# Audio.net
KiCad netlist of a schematic drawn in Altium Designer
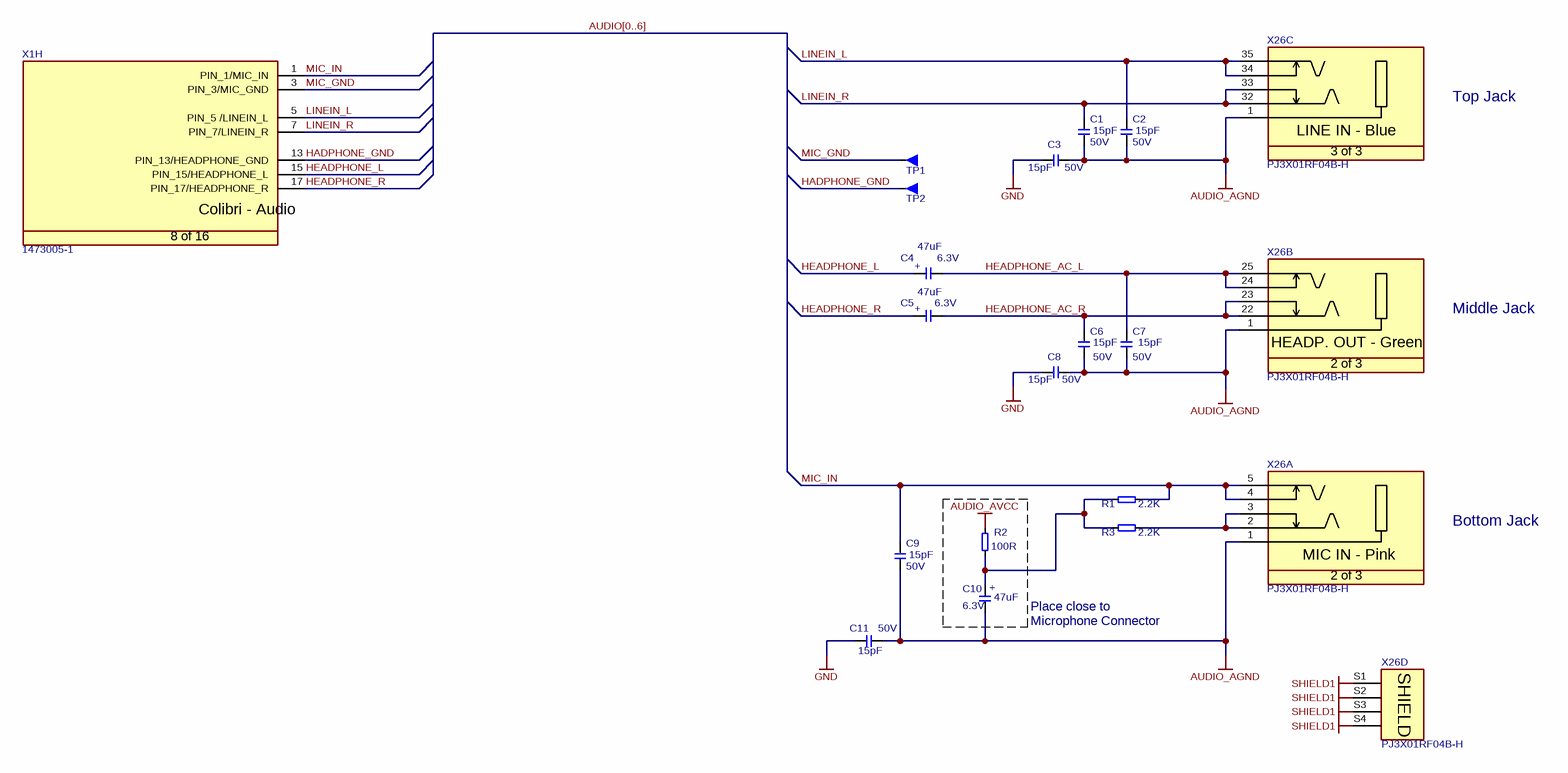
[diagram p0: Audio.SchDoc]

(export (version "E")
  (design (tool "Eeschema 10.0.6"))
  (components
    (comp (ref "C1")
      (value "15pF")
      (footprint "T_CAPC0603X33N")
      (description "Capacitor Ceramic NPO 15pF 50V 10% 0603")
      (fields (field (name "TOLERANCE") "10%") (field (name "RATING") "50V"))
      (libsource (lib "Evaluation Board") (part "C-NPO-15pF-50V-10%-0603"))
    )
    (comp (ref "C2")
      (value "15pF")
      (footprint "T_CAPC0603X33N")
      (description "Capacitor Ceramic NPO 15pF 50V 10% 0603")
      (fields (field (name "TOLERANCE") "10%") (field (name "RATING") "50V"))
      (libsource (lib "Evaluation Board") (part "C-NPO-15pF-50V-10%-0603"))
    )
    (comp (ref "C3")
      (value "15pF")
      (footprint "T_CAPC0603X33N")
      (description "Capacitor Ceramic NPO 15pF 50V 10% 0603")
      (fields (field (name "TOLERANCE") "10%") (field (name "RATING") "50V"))
      (libsource (lib "Evaluation Board") (part "C-NPO-15pF-50V-10%-0603"))
    )
    (comp (ref "C4")
      (value "47uF")
      (footprint "CAPMP3528X210N")
      (description "Capacitor TA 47uF 6.3V 20% 3216")
      (fields (field (name "TOLERANCE") "20%") (field (name "RATING") "6.3V"))
      (libsource (lib "Evaluation Board") (part "C-TA-47uF-6.3V-20%-3216"))
    )
    (comp (ref "C5")
      (value "47uF")
      (footprint "CAPMP3528X210N")
      (description "Capacitor TA 47uF 6.3V 20% 3216")
      (fields (field (name "TOLERANCE") "20%") (field (name "RATING") "6.3V"))
      (libsource (lib "Evaluation Board") (part "C-TA-47uF-6.3V-20%-3216"))
    )
    (comp (ref "C6")
      (value "15pF")
      (footprint "T_CAPC0603X33N")
      (description "Capacitor Ceramic NPO 15pF 50V 10% 0603")
      (fields (field (name "TOLERANCE") "10%") (field (name "RATING") "50V"))
      (libsource (lib "Evaluation Board") (part "C-NPO-15pF-50V-10%-0603"))
    )
    (comp (ref "C7")
      (value "15pF")
      (footprint "T_CAPC0603X33N")
      (description "Capacitor Ceramic NPO 15pF 50V 10% 0603")
      (fields (field (name "TOLERANCE") "10%") (field (name "RATING") "50V"))
      (libsource (lib "Evaluation Board") (part "C-NPO-15pF-50V-10%-0603"))
    )
    (comp (ref "C8")
      (value "15pF")
      (footprint "T_CAPC0603X33N")
      (description "Capacitor Ceramic NPO 15pF 50V 10% 0603")
      (fields (field (name "TOLERANCE") "10%") (field (name "RATING") "50V"))
      (libsource (lib "Evaluation Board") (part "C-NPO-15pF-50V-10%-0603"))
    )
    (comp (ref "C9")
      (value "15pF")
      (footprint "T_CAPC0603X33N")
      (description "Capacitor Ceramic NPO 15pF 50V 10% 0603")
      (fields (field (name "TOLERANCE") "10%") (field (name "RATING") "50V"))
      (libsource (lib "Evaluation Board") (part "C-NPO-15pF-50V-10%-0603"))
    )
    (comp (ref "C10")
      (value "47uF")
      (footprint "CAPMP3528X210N")
      (description "Capacitor TA 47uF 6.3V 20% 3216")
      (fields (field (name "TOLERANCE") "20%") (field (name "RATING") "6.3V"))
      (libsource (lib "Evaluation Board") (part "C-TA-47uF-6.3V-20%-3216"))
    )
    (comp (ref "C11")
      (value "15pF")
      (footprint "T_CAPC0603X33N")
      (description "Capacitor Ceramic NPO 15pF 50V 10% 0603")
      (fields (field (name "TOLERANCE") "10%") (field (name "RATING") "50V"))
      (libsource (lib "Evaluation Board") (part "C-NPO-15pF-50V-10%-0603"))
    )
    (comp (ref "R1")
      (value "2.2K")
      (footprint "T_RESC0603X30N")
      (description "Resistor 2.2Kohm 63mW 5% 0603")
      (fields (field (name "TOLERANCE") "5%"))
      (libsource (lib "Evaluation Board") (part "R-2.2KR-63mW-5%-0603"))
    )
    (comp (ref "R2")
      (value "100R")
      (footprint "T_RESC0603X30N")
      (description "Resistor 100 ohm 63mW 5% 0603")
      (fields (field (name "TOLERANCE") "5%"))
      (libsource (lib "Evaluation Board") (part "R-100R-63mW-5%-0603"))
    )
    (comp (ref "R3")
      (value "2.2K")
      (footprint "T_RESC0603X30N")
      (description "Resistor 2.2Kohm 63mW 5% 0603")
      (fields (field (name "TOLERANCE") "5%"))
      (libsource (lib "Evaluation Board") (part "R-2.2KR-63mW-5%-0603"))
    )
    (comp (ref "TP1")
      (value "Testpin")
      (footprint "T_TP-THT")
      (description "Testpin TH")
      (libsource (lib "Evaluation Board") (part "Testpin"))
    )
    (comp (ref "TP2")
      (value "Testpin")
      (footprint "T_TP-THT")
      (description "Testpin TH")
      (libsource (lib "Evaluation Board") (part "Testpin"))
    )
    (comp (ref "X1")
      (value "CON-Tyco-1473005-1-200-0.6mm")
      (footprint "T_Tyco_1473005-1")
      (description "SODIMM Connector")
      (fields (field (name "MANUFACTURER PART NO.") "1473005-1"))
      (libsource (lib "Evaluation Board") (part "CON-Tyco-1473005-1-200-0.6mm"))
    )
    (comp (ref "X26")
      (value "AUK-PJ3X01RF04B-H")
      (footprint "T_AUK_PJ3X01RF04B-H")
      (description "3x Audiojack stereo, 3.5mm")
      (fields (field (name "MANUFACTURER PART NO.") "PJ3X01RF04B-H"))
      (libsource (lib "Evaluation Board") (part "CON-AUK-PJ3X01RF04B-H"))
    )
  )
  (nets
    (net (code "9") (name "/HADPHONE_GND") (class "Default")
      (node (ref "TP2") (pin "1") (pinfunction "1_1") (pintype "passive"))
      (node (ref "X1") (pin "13") (pinfunction "PIN_13/HEADPHONE_GND_13") (pintype "passive"))
    )
    (net (code "10") (name "/HEADPHONE_AC_L") (class "Default")
      (node (ref "C4") (pin "2") (pinfunction "2_2") (pintype "passive"))
      (node (ref "C7") (pin "2") (pinfunction "2_2") (pintype "passive"))
      (node (ref "X26") (pin "24") (pinfunction "24_24") (pintype "passive"))
      (node (ref "X26") (pin "25") (pinfunction "25_25") (pintype "passive"))
    )
    (net (code "11") (name "/HEADPHONE_AC_R") (class "Default")
      (node (ref "C5") (pin "2") (pinfunction "2_2") (pintype "passive"))
      (node (ref "C6") (pin "2") (pinfunction "2_2") (pintype "passive"))
      (node (ref "X26") (pin "22") (pinfunction "22_22") (pintype "passive"))
      (node (ref "X26") (pin "23") (pinfunction "23_23") (pintype "passive"))
    )
    (net (code "12") (name "/HEADPHONE_L") (class "Default")
      (node (ref "C4") (pin "1") (pinfunction "1_1") (pintype "passive"))
      (node (ref "X1") (pin "15") (pinfunction "PIN_15/HEADPHONE_L_15") (pintype "passive"))
    )
    (net (code "13") (name "/HEADPHONE_R") (class "Default")
      (node (ref "C5") (pin "1") (pinfunction "1_1") (pintype "passive"))
      (node (ref "X1") (pin "17") (pinfunction "PIN_17/HEADPHONE_R_17") (pintype "passive"))
    )
    (net (code "14") (name "/LINEIN_L") (class "Default")
      (node (ref "C2") (pin "2") (pinfunction "2_2") (pintype "passive"))
      (node (ref "X1") (pin "5") (pinfunction "PIN_5_/LINEIN_L_5") (pintype "passive"))
      (node (ref "X26") (pin "34") (pinfunction "34_34") (pintype "passive"))
      (node (ref "X26") (pin "35") (pinfunction "35_35") (pintype "passive"))
    )
    (net (code "15") (name "/LINEIN_R") (class "Default")
      (node (ref "C1") (pin "2") (pinfunction "2_2") (pintype "passive"))
      (node (ref "X1") (pin "7") (pinfunction "PIN_7/LINEIN_R_7") (pintype "passive"))
      (node (ref "X26") (pin "32") (pinfunction "32_32") (pintype "passive"))
      (node (ref "X26") (pin "33") (pinfunction "33_33") (pintype "passive"))
    )
    (net (code "16") (name "/MIC_GND") (class "Default")
      (node (ref "TP1") (pin "1") (pinfunction "1_1") (pintype "passive"))
      (node (ref "X1") (pin "3") (pinfunction "PIN_3/MIC_GND_3") (pintype "passive"))
    )
    (net (code "17") (name "/MIC_IN") (class "Default")
      (node (ref "C9") (pin "2") (pinfunction "2_2") (pintype "passive"))
      (node (ref "R1") (pin "2") (pinfunction "2_2") (pintype "passive"))
      (node (ref "X1") (pin "1") (pinfunction "PIN_1/MIC_IN_1") (pintype "passive"))
      (node (ref "X26") (pin "4") (pinfunction "4_4") (pintype "passive"))
      (node (ref "X26") (pin "5") (pinfunction "5_5") (pintype "passive"))
    )
    (net (code "18") (name "AUDIO_AGND") (class "Default")
      (node (ref "C1") (pin "1") (pinfunction "1_1") (pintype "passive"))
      (node (ref "C10") (pin "2") (pinfunction "2_2") (pintype "passive"))
      (node (ref "C11") (pin "1") (pinfunction "1_1") (pintype "passive"))
      (node (ref "C2") (pin "1") (pinfunction "1_1") (pintype "passive"))
      (node (ref "C3") (pin "2") (pinfunction "2_2") (pintype "passive"))
      (node (ref "C6") (pin "1") (pinfunction "1_1") (pintype "passive"))
      (node (ref "C7") (pin "1") (pinfunction "1_1") (pintype "passive"))
      (node (ref "C8") (pin "2") (pinfunction "2_2") (pintype "passive"))
      (node (ref "C9") (pin "1") (pinfunction "1_1") (pintype "passive"))
      (node (ref "X26") (pin "1") (pinfunction "1_1") (pintype "passive"))
    )
    (net (code "19") (name "AUDIO_AVCC") (class "Default")
      (node (ref "R2") (pin "2") (pinfunction "2_2") (pintype "passive"))
    )
    (net (code "20") (name "GND") (class "Default")
      (node (ref "C11") (pin "2") (pinfunction "2_2") (pintype "passive"))
      (node (ref "C3") (pin "1") (pinfunction "1_1") (pintype "passive"))
      (node (ref "C8") (pin "1") (pinfunction "1_1") (pintype "passive"))
    )
    (net (code "21") (name "Net-(C10-Pad1)") (class "Default")
      (node (ref "C10") (pin "1") (pinfunction "1_1") (pintype "passive"))
      (node (ref "R1") (pin "1") (pinfunction "1_1") (pintype "passive"))
      (node (ref "R2") (pin "1") (pinfunction "1_1") (pintype "passive"))
      (node (ref "R3") (pin "1") (pinfunction "1_1") (pintype "passive"))
    )
    (net (code "22") (name "Net-(R3-Pad2)") (class "Default")
      (node (ref "R3") (pin "2") (pinfunction "2_2") (pintype "passive"))
      (node (ref "X26") (pin "2") (pinfunction "2_2") (pintype "passive"))
      (node (ref "X26") (pin "3") (pinfunction "3_3") (pintype "passive"))
    )
    (net (code "23") (name "SHIELD1") (class "Default")
      (node (ref "X26") (pin "S1") (pinfunction "SHIELD_S1") (pintype "passive"))
      (node (ref "X26") (pin "S2") (pinfunction "SHIELD_S2") (pintype "passive"))
      (node (ref "X26") (pin "S3") (pinfunction "SHIELD_S3") (pintype "passive"))
      (node (ref "X26") (pin "S4") (pinfunction "SHIELD_S4") (pintype "passive"))
    )
  )
)
